# Stand_Sensor.net
KiCad netlist of a schematic drawn in EAGLE
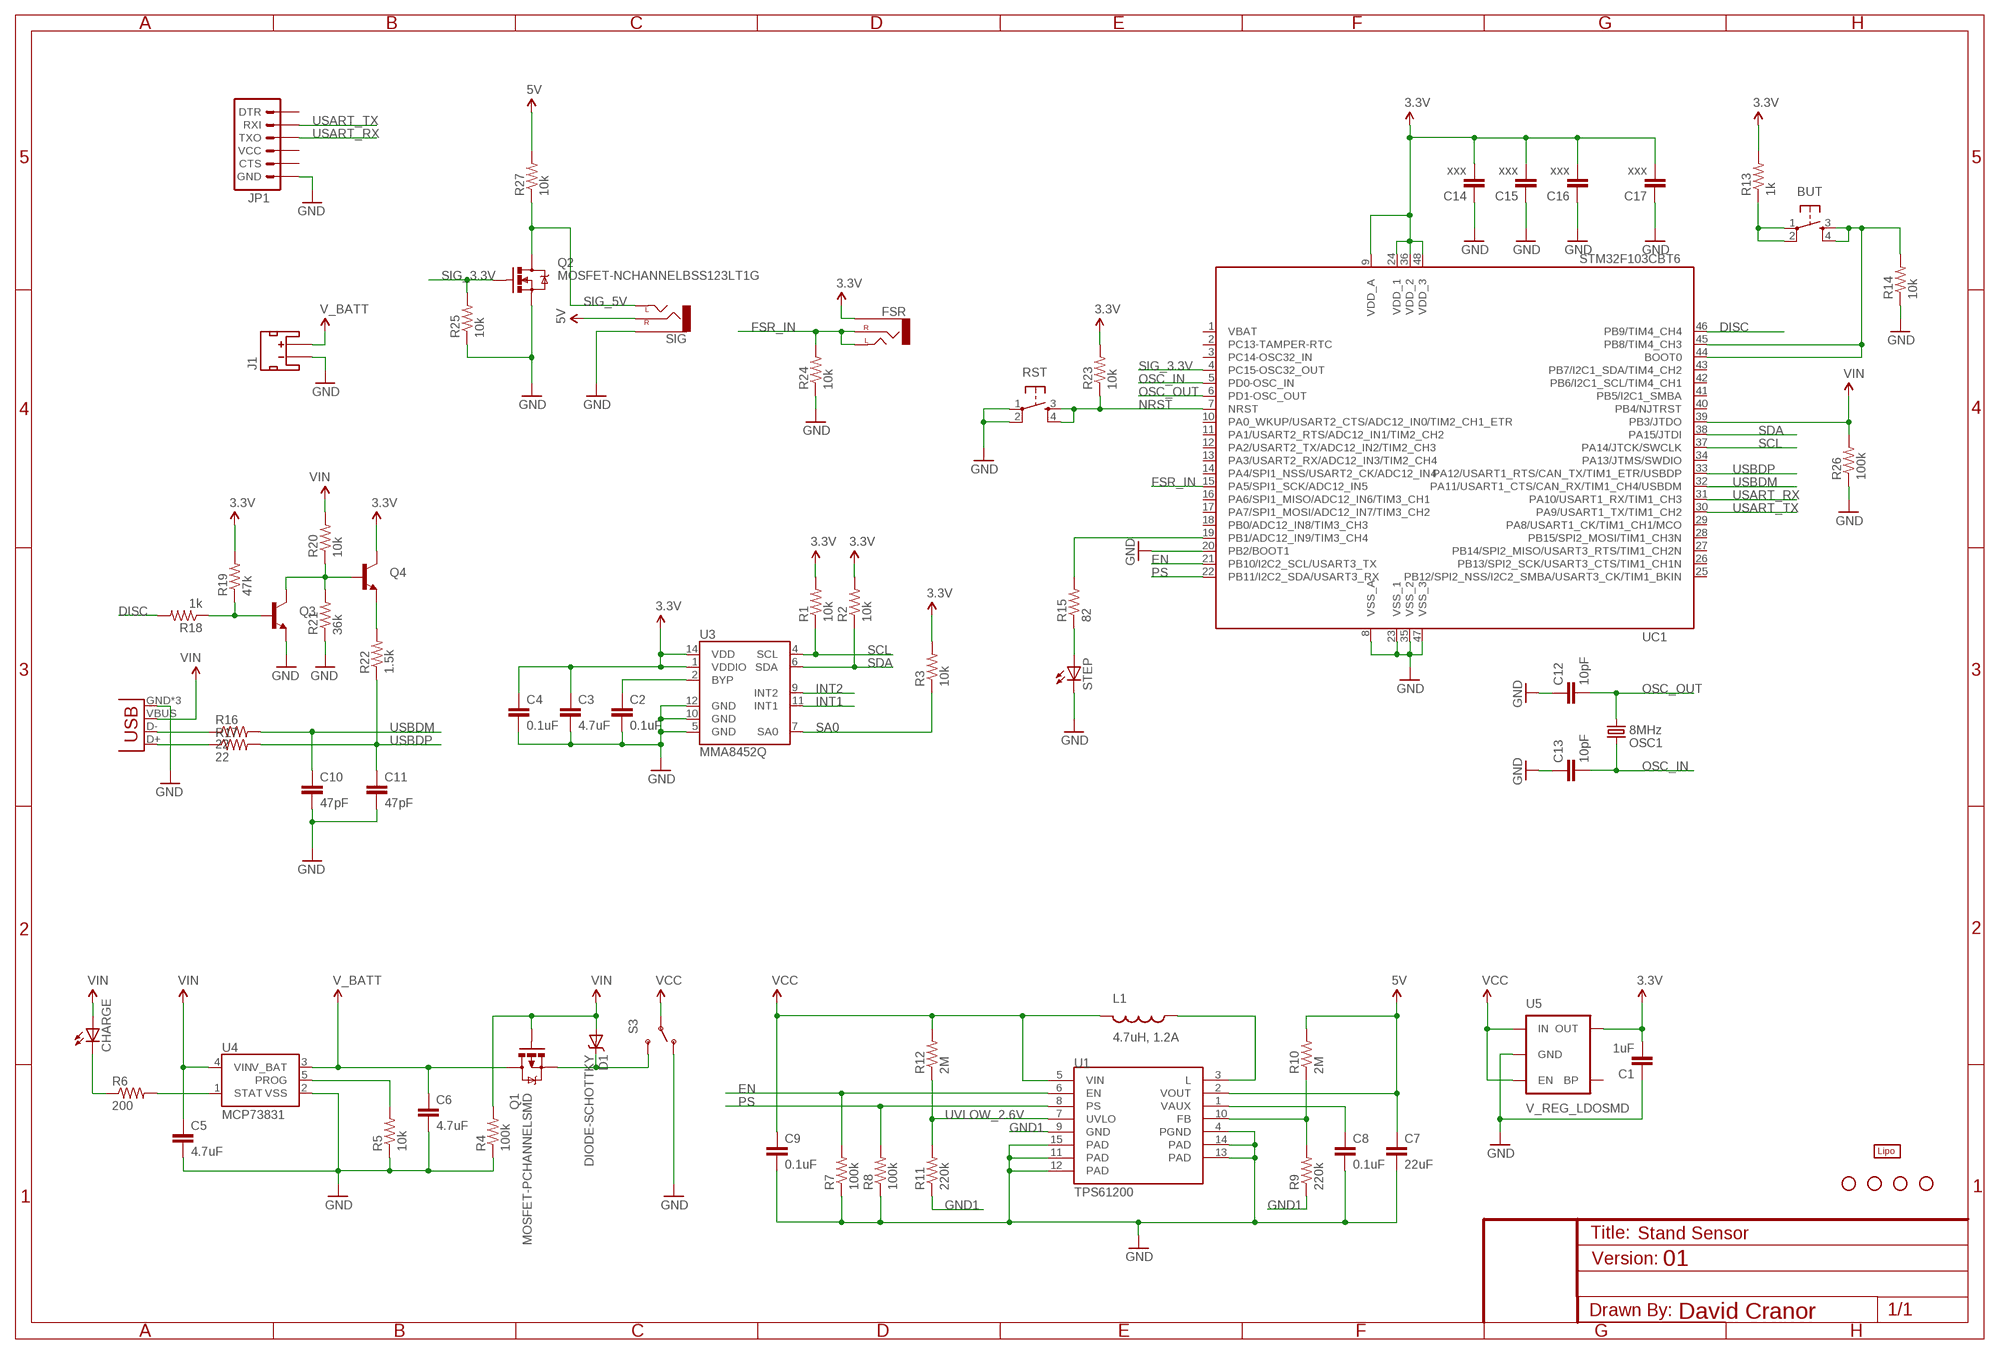
[diagram p0: schematic, sheet 1]

(export (version "E")
  (design (tool "Eeschema 10.0.6"))
  (components
    (comp (ref "BUT")
      (value "TAC_SWITCHSMD")
      (footprint "eagle-import:TACTILE_SWITCH_SMD")
      (libsource (lib "eagle-import") (part "TAC_SWITCHSMD"))
    )
    (comp (ref "C1")
      (value "1uF")
      (footprint "eagle-import:1206")
      (libsource (lib "eagle-import") (part "CAP1206"))
    )
    (comp (ref "C2")
      (value "0.1uF")
      (footprint "eagle-import:1206")
      (libsource (lib "eagle-import") (part "CAP1206"))
    )
    (comp (ref "C3")
      (value "4.7uF")
      (footprint "eagle-import:1206")
      (libsource (lib "eagle-import") (part "CAP1206"))
    )
    (comp (ref "C4")
      (value "0.1uF")
      (footprint "eagle-import:1206")
      (libsource (lib "eagle-import") (part "CAP1206"))
    )
    (comp (ref "C5")
      (value "4.7uF")
      (footprint "eagle-import:1206")
      (libsource (lib "eagle-import") (part "CAP1206"))
    )
    (comp (ref "C6")
      (value "4.7uF")
      (footprint "eagle-import:1206")
      (libsource (lib "eagle-import") (part "CAP1206"))
    )
    (comp (ref "C7")
      (value "22uF")
      (footprint "eagle-import:1206")
      (libsource (lib "eagle-import") (part "CAP1206"))
    )
    (comp (ref "C8")
      (value "0.1uF")
      (footprint "eagle-import:1206")
      (libsource (lib "eagle-import") (part "CAP1206"))
    )
    (comp (ref "C9")
      (value "0.1uF")
      (footprint "eagle-import:1206")
      (libsource (lib "eagle-import") (part "CAP1206"))
    )
    (comp (ref "C10")
      (value "47pF")
      (footprint "eagle-import:1206")
      (libsource (lib "eagle-import") (part "CAP1206"))
    )
    (comp (ref "C11")
      (value "47pF")
      (footprint "eagle-import:1206")
      (libsource (lib "eagle-import") (part "CAP1206"))
    )
    (comp (ref "C12")
      (value "10pF")
      (footprint "eagle-import:1206")
      (libsource (lib "eagle-import") (part "CAP1206"))
    )
    (comp (ref "C13")
      (value "10pF")
      (footprint "eagle-import:1206")
      (libsource (lib "eagle-import") (part "CAP1206"))
    )
    (comp (ref "C14")
      (value "xxx")
      (footprint "eagle-import:1206")
      (libsource (lib "eagle-import") (part "CAP1206"))
    )
    (comp (ref "C15")
      (value "xxx")
      (footprint "eagle-import:1206")
      (libsource (lib "eagle-import") (part "CAP1206"))
    )
    (comp (ref "C16")
      (value "xxx")
      (footprint "eagle-import:1206")
      (libsource (lib "eagle-import") (part "CAP1206"))
    )
    (comp (ref "C17")
      (value "xxx")
      (footprint "eagle-import:1206")
      (libsource (lib "eagle-import") (part "CAP1206"))
    )
    (comp (ref "CHARGE")
      (value "LED1206")
      (footprint "eagle-import:LED-1206")
      (libsource (lib "eagle-import") (part "LED1206"))
    )
    (comp (ref "D1")
      (value "DIODE-SCHOTTKY")
      (footprint "eagle-import:SOD-523")
      (libsource (lib "eagle-import") (part "DIODE-SCHOTTKY"))
    )
    (comp (ref "FSR")
      (value "AUDIO-JACKPTH")
      (footprint "eagle-import:AUDIO-JACK")
      (libsource (lib "eagle-import") (part "AUDIO-JACKPTH"))
    )
    (comp (ref "J1")
      (value "JST_2MM_MALE")
      (footprint "eagle-import:JST-2-SMD")
      (libsource (lib "eagle-import") (part "JST_2MM_MALE"))
    )
    (comp (ref "JP1")
      (value "ARDUINO_SERIAL_PROGRAMSMD")
      (footprint "eagle-import:1X06-SMD")
      (libsource (lib "eagle-import") (part "ARDUINO_SERIAL_PROGRAMSMD"))
    )
    (comp (ref "L1")
      (value "4.7uH, 1.2A")
      (footprint "eagle-import:CDRH2D09")
      (libsource (lib "eagle-import") (part "INDUCTOR."))
    )
    (comp (ref "OSC1")
      (value "8MHz")
      (footprint "eagle-import:CRYSTAL-SMD-5X3")
      (libsource (lib "eagle-import") (part "CRYSTAL5X3"))
    )
    (comp (ref "Q1")
      (value "MOSFET-PCHANNELSMD")
      (footprint "eagle-import:SOT23-3")
      (libsource (lib "eagle-import") (part "MOSFET-PCHANNELSMD"))
    )
    (comp (ref "Q2")
      (value "MOSFET-NCHANNELBSS123LT1G")
      (footprint "eagle-import:SOT23")
      (libsource (lib "eagle-import") (part "MOSFET-NCHANNELBSS123LT1G"))
    )
    (comp (ref "Q3")
      (value "TRANSISTOR_NPNSOT23")
      (footprint "eagle-import:SOT23")
      (libsource (lib "eagle-import") (part "TRANSISTOR_NPNSOT23"))
    )
    (comp (ref "Q4")
      (value "TRANSISTOR_NPNSOT23")
      (footprint "eagle-import:SOT23")
      (libsource (lib "eagle-import") (part "TRANSISTOR_NPNSOT23"))
    )
    (comp (ref "R1")
      (value "10k")
      (footprint "eagle-import:1206")
      (libsource (lib "eagle-import") (part "RESISTOR1206"))
    )
    (comp (ref "R2")
      (value "10k")
      (footprint "eagle-import:1206")
      (libsource (lib "eagle-import") (part "RESISTOR1206"))
    )
    (comp (ref "R3")
      (value "10k")
      (footprint "eagle-import:1206")
      (libsource (lib "eagle-import") (part "RESISTOR1206"))
    )
    (comp (ref "R4")
      (value "100k")
      (footprint "eagle-import:1206")
      (libsource (lib "eagle-import") (part "RESISTOR1206"))
    )
    (comp (ref "R5")
      (value "10k")
      (footprint "eagle-import:1206")
      (libsource (lib "eagle-import") (part "RESISTOR1206"))
    )
    (comp (ref "R6")
      (value "200")
      (footprint "eagle-import:1206")
      (libsource (lib "eagle-import") (part "RESISTOR1206"))
    )
    (comp (ref "R7")
      (value "100k")
      (footprint "eagle-import:1206")
      (libsource (lib "eagle-import") (part "RESISTOR1206"))
    )
    (comp (ref "R8")
      (value "100k")
      (footprint "eagle-import:1206")
      (libsource (lib "eagle-import") (part "RESISTOR1206"))
    )
    (comp (ref "R9")
      (value "220k")
      (footprint "eagle-import:1206")
      (libsource (lib "eagle-import") (part "RESISTOR1206"))
    )
    (comp (ref "R10")
      (value "2M")
      (footprint "eagle-import:1206")
      (libsource (lib "eagle-import") (part "RESISTOR1206"))
    )
    (comp (ref "R11")
      (value "220k")
      (footprint "eagle-import:1206")
      (libsource (lib "eagle-import") (part "RESISTOR1206"))
    )
    (comp (ref "R12")
      (value "2M")
      (footprint "eagle-import:1206")
      (libsource (lib "eagle-import") (part "RESISTOR1206"))
    )
    (comp (ref "R13")
      (value "1k")
      (footprint "eagle-import:1206")
      (libsource (lib "eagle-import") (part "RESISTOR1206"))
    )
    (comp (ref "R14")
      (value "10k")
      (footprint "eagle-import:1206")
      (libsource (lib "eagle-import") (part "RESISTOR1206"))
    )
    (comp (ref "R15")
      (value "82")
      (footprint "eagle-import:1206")
      (libsource (lib "eagle-import") (part "RESISTOR1206"))
    )
    (comp (ref "R16")
      (value "22")
      (footprint "eagle-import:1206")
      (libsource (lib "eagle-import") (part "RESISTOR1206"))
    )
    (comp (ref "R17")
      (value "22")
      (footprint "eagle-import:1206")
      (libsource (lib "eagle-import") (part "RESISTOR1206"))
    )
    (comp (ref "R18")
      (value "1k")
      (footprint "eagle-import:1206")
      (libsource (lib "eagle-import") (part "RESISTOR1206"))
    )
    (comp (ref "R19")
      (value "47k")
      (footprint "eagle-import:1206")
      (libsource (lib "eagle-import") (part "RESISTOR1206"))
    )
    (comp (ref "R20")
      (value "10k")
      (footprint "eagle-import:1206")
      (libsource (lib "eagle-import") (part "RESISTOR1206"))
    )
    (comp (ref "R21")
      (value "36k")
      (footprint "eagle-import:1206")
      (libsource (lib "eagle-import") (part "RESISTOR1206"))
    )
    (comp (ref "R22")
      (value "1.5k")
      (footprint "eagle-import:1206")
      (libsource (lib "eagle-import") (part "RESISTOR1206"))
    )
    (comp (ref "R23")
      (value "10k")
      (footprint "eagle-import:1206")
      (libsource (lib "eagle-import") (part "RESISTOR1206"))
    )
    (comp (ref "R24")
      (value "10k")
      (footprint "eagle-import:1206")
      (libsource (lib "eagle-import") (part "RESISTOR1206"))
    )
    (comp (ref "R25")
      (value "10k")
      (footprint "eagle-import:1206")
      (libsource (lib "eagle-import") (part "RESISTOR1206"))
    )
    (comp (ref "R26")
      (value "100k")
      (footprint "eagle-import:1206")
      (libsource (lib "eagle-import") (part "RESISTOR1206"))
    )
    (comp (ref "R27")
      (value "10k")
      (footprint "eagle-import:1206")
      (libsource (lib "eagle-import") (part "RESISTOR1206"))
    )
    (comp (ref "RST")
      (value "TAC_SWITCHSMD")
      (footprint "eagle-import:TACTILE_SWITCH_SMD")
      (libsource (lib "eagle-import") (part "TAC_SWITCHSMD"))
    )
    (comp (ref "S3")
      (value "SWITCH-SPDTSMD")
      (footprint "eagle-import:AYZ0202")
      (libsource (lib "eagle-import") (part "SWITCH-SPDTSMD"))
    )
    (comp (ref "SIG")
      (value "AUDIO-JACKPTH")
      (footprint "eagle-import:AUDIO-JACK")
      (libsource (lib "eagle-import") (part "AUDIO-JACKPTH"))
    )
    (comp (ref "STANDOFF1")
      (value "STAND-OFF")
      (footprint "eagle-import:STAND-OFF")
      (libsource (lib "eagle-import") (part "STAND-OFF"))
    )
    (comp (ref "STANDOFF2")
      (value "STAND-OFF")
      (footprint "eagle-import:STAND-OFF")
      (libsource (lib "eagle-import") (part "STAND-OFF"))
    )
    (comp (ref "STANDOFF3")
      (value "STAND-OFF")
      (footprint "eagle-import:STAND-OFF")
      (libsource (lib "eagle-import") (part "STAND-OFF"))
    )
    (comp (ref "STANDOFF4")
      (value "STAND-OFF")
      (footprint "eagle-import:STAND-OFF")
      (libsource (lib "eagle-import") (part "STAND-OFF"))
    )
    (comp (ref "STEP")
      (value "LED1206")
      (footprint "eagle-import:LED-1206")
      (libsource (lib "eagle-import") (part "LED1206"))
    )
    (comp (ref "U$1")
      (value "LIPO-OUTLINE2000")
      (footprint "eagle-import:LIPO-2000")
      (libsource (lib "eagle-import") (part "LIPO-OUTLINE2000"))
    )
    (comp (ref "U1")
      (value "TPS61200")
      (footprint "eagle-import:QFN-10_PAD")
      (libsource (lib "eagle-import") (part "TPS61200"))
    )
    (comp (ref "U3")
      (value "MMA8452Q")
      (footprint "eagle-import:QFN-16_0.5MM")
      (libsource (lib "eagle-import") (part "MMA8452Q"))
    )
    (comp (ref "U4")
      (value "MCP73831")
      (footprint "eagle-import:SOT23-5")
      (libsource (lib "eagle-import") (part "MCP73831"))
    )
    (comp (ref "U5")
      (value "V_REG_LDOSMD")
      (footprint "eagle-import:SOT23-5")
      (libsource (lib "eagle-import") (part "V_REG_LDOSMD"))
    )
    (comp (ref "UC1")
      (value "STM32F103CBT6")
      (footprint "eagle-import:LQFP48")
      (libsource (lib "eagle-import") (part "STM32F103CB"))
    )
    (comp (ref "USB")
      (value "USB-MICROB")
      (footprint "eagle-import:USB-MICROB")
      (libsource (lib "eagle-import") (part "USB-MICROB"))
    )
  )
  (nets
    (net (code "1") (name "/DISC") (class "Default")
      (node (ref "R18") (pin "2") (pinfunction "2_2") (pintype "passive"))
      (node (ref "UC1") (pin "46") (pinfunction "PB9/TIM4_CH4_46") (pintype "input"))
    )
    (net (code "2") (name "/EN") (class "Default")
      (node (ref "R7") (pin "2") (pinfunction "2_2") (pintype "passive"))
      (node (ref "U1") (pin "6") (pinfunction "EN_6") (pintype "input"))
      (node (ref "UC1") (pin "21") (pinfunction "PB10/I2C2_SCL/USART3_TX_21") (pintype "input"))
    )
    (net (code "3") (name "/FSR_IN") (class "Default")
      (node (ref "FSR") (pin "RING") (pinfunction "RIGHT_RING") (pintype "bidirectional"))
      (node (ref "FSR") (pin "TIP") (pinfunction "LEFT_TIP") (pintype "bidirectional"))
      (node (ref "R24") (pin "2") (pinfunction "2_2") (pintype "passive"))
      (node (ref "UC1") (pin "15") (pinfunction "PA5/SPI1_SCK/ADC12_IN5_15") (pintype "bidirectional"))
    )
    (net (code "4") (name "/GND1") (class "Default")
      (node (ref "R11") (pin "1") (pinfunction "1_1") (pintype "passive"))
      (node (ref "R9") (pin "1") (pinfunction "1_1") (pintype "passive"))
      (node (ref "U1") (pin "9") (pinfunction "GND_9") (pintype "power_in"))
    )
    (net (code "5") (name "/INT1") (class "Default")
      (node (ref "U3") (pin "11") (pinfunction "INT1_11") (pintype "bidirectional"))
    )
    (net (code "6") (name "/INT2") (class "Default")
      (node (ref "U3") (pin "9") (pinfunction "INT2_9") (pintype "bidirectional"))
    )
    (net (code "7") (name "/NRST") (class "Default")
      (node (ref "R23") (pin "1") (pinfunction "1_1") (pintype "passive"))
      (node (ref "RST") (pin "3") (pinfunction "3_3") (pintype "passive"))
      (node (ref "RST") (pin "4") (pinfunction "4_4") (pintype "passive"))
      (node (ref "UC1") (pin "7") (pinfunction "NRST_7") (pintype "input"))
    )
    (net (code "8") (name "/OSC_IN") (class "Default")
      (node (ref "C13") (pin "2") (pinfunction "2_2") (pintype "passive"))
      (node (ref "OSC1") (pin "3") (pinfunction "2_3") (pintype "passive"))
      (node (ref "UC1") (pin "5") (pinfunction "PD0-OSC_IN_5") (pintype "input"))
    )
    (net (code "9") (name "/OSC_OUT") (class "Default")
      (node (ref "C12") (pin "2") (pinfunction "2_2") (pintype "passive"))
      (node (ref "OSC1") (pin "1") (pinfunction "1_1") (pintype "passive"))
      (node (ref "UC1") (pin "6") (pinfunction "PD1-OSC_OUT_6") (pintype "input"))
    )
    (net (code "10") (name "/PS") (class "Default")
      (node (ref "R8") (pin "2") (pinfunction "2_2") (pintype "passive"))
      (node (ref "U1") (pin "8") (pinfunction "PS_8") (pintype "input"))
      (node (ref "UC1") (pin "22") (pinfunction "PB11/I2C2_SDA/USART3_RX_22") (pintype "input"))
    )
    (net (code "11") (name "/SA0") (class "Default")
      (node (ref "R3") (pin "1") (pinfunction "1_1") (pintype "passive"))
      (node (ref "U3") (pin "7") (pinfunction "SA0_7") (pintype "bidirectional"))
    )
    (net (code "12") (name "/SCL") (class "Default")
      (node (ref "R1") (pin "1") (pinfunction "1_1") (pintype "passive"))
      (node (ref "U3") (pin "4") (pinfunction "SCL_4") (pintype "bidirectional"))
      (node (ref "UC1") (pin "37") (pinfunction "PA14/JTCK/SWCLK_37") (pintype "bidirectional"))
    )
    (net (code "13") (name "/SDA") (class "Default")
      (node (ref "R2") (pin "1") (pinfunction "1_1") (pintype "passive"))
      (node (ref "U3") (pin "6") (pinfunction "SDA_6") (pintype "bidirectional"))
      (node (ref "UC1") (pin "38") (pinfunction "PA15/JTDI_38") (pintype "bidirectional"))
    )
    (net (code "14") (name "/SIG_3.3V") (class "Default")
      (node (ref "Q2") (pin "1") (pinfunction "G_1") (pintype "passive"))
      (node (ref "R25") (pin "2") (pinfunction "2_2") (pintype "passive"))
      (node (ref "UC1") (pin "4") (pinfunction "PC15-OSC32_OUT_4") (pintype "input"))
    )
    (net (code "15") (name "/SIG_5V") (class "Default")
      (node (ref "Q2") (pin "3") (pinfunction "D_3") (pintype "passive"))
      (node (ref "R27") (pin "1") (pinfunction "1_1") (pintype "passive"))
      (node (ref "SIG") (pin "TIP") (pinfunction "LEFT_TIP") (pintype "bidirectional"))
    )
    (net (code "16") (name "/USART_RX") (class "Default")
      (node (ref "JP1") (pin "3") (pinfunction "TXO_3") (pintype "passive"))
      (node (ref "UC1") (pin "31") (pinfunction "PA10/USART1_RX/TIM1_CH3_31") (pintype "bidirectional"))
    )
    (net (code "17") (name "/USART_TX") (class "Default")
      (node (ref "JP1") (pin "2") (pinfunction "RXI_2") (pintype "passive"))
      (node (ref "UC1") (pin "30") (pinfunction "PA9/USART1_TX/TIM1_CH2_30") (pintype "input"))
    )
    (net (code "18") (name "/USBDM") (class "Default")
      (node (ref "C10") (pin "1") (pinfunction "1_1") (pintype "passive"))
      (node (ref "R16") (pin "2") (pinfunction "2_2") (pintype "passive"))
      (node (ref "UC1") (pin "32") (pinfunction "PA11/USART1_CTS/CAN_RX/TIM1_CH4/USBDM_32") (pintype "bidirectional"))
    )
    (net (code "19") (name "/USBDP") (class "Default")
      (node (ref "C11") (pin "1") (pinfunction "1_1") (pintype "passive"))
      (node (ref "R17") (pin "2") (pinfunction "2_2") (pintype "passive"))
      (node (ref "R22") (pin "1") (pinfunction "1_1") (pintype "passive"))
      (node (ref "UC1") (pin "33") (pinfunction "PA12/USART1_RTS/CAN_TX/TIM1_ETR/USBDP_33") (pintype "bidirectional"))
    )
    (net (code "20") (name "/UVLOW_2.6V") (class "Default")
      (node (ref "R11") (pin "2") (pinfunction "2_2") (pintype "passive"))
      (node (ref "R12") (pin "1") (pinfunction "1_1") (pintype "passive"))
      (node (ref "U1") (pin "7") (pinfunction "UVLO_7") (pintype "passive"))
    )
    (net (code "21") (name "/VBAT") (class "Default")
      (node (ref "UC1") (pin "1") (pinfunction "VBAT_1") (pintype "power_in"))
    )
    (net (code "22") (name "3.3V") (class "Default")
      (node (ref "C1") (pin "2") (pinfunction "2_2") (pintype "passive"))
      (node (ref "C14") (pin "2") (pinfunction "2_2") (pintype "passive"))
      (node (ref "C15") (pin "2") (pinfunction "2_2") (pintype "passive"))
      (node (ref "C16") (pin "2") (pinfunction "2_2") (pintype "passive"))
      (node (ref "C17") (pin "2") (pinfunction "2_2") (pintype "passive"))
      (node (ref "C3") (pin "1") (pinfunction "1_1") (pintype "passive"))
      (node (ref "C4") (pin "1") (pinfunction "1_1") (pintype "passive"))
      (node (ref "FSR") (pin "SLEEVE") (pinfunction "SLEEVE_SLEEVE") (pintype "bidirectional"))
      (node (ref "Q4") (pin "3") (pinfunction "C_3") (pintype "passive"))
      (node (ref "R1") (pin "2") (pinfunction "2_2") (pintype "passive"))
      (node (ref "R13") (pin "2") (pinfunction "2_2") (pintype "passive"))
      (node (ref "R19") (pin "2") (pinfunction "2_2") (pintype "passive"))
      (node (ref "R2") (pin "2") (pinfunction "2_2") (pintype "passive"))
      (node (ref "R23") (pin "2") (pinfunction "2_2") (pintype "passive"))
      (node (ref "R3") (pin "2") (pinfunction "2_2") (pintype "passive"))
      (node (ref "U3") (pin "1") (pinfunction "VDDIO_1") (pintype "bidirectional"))
      (node (ref "U3") (pin "14") (pinfunction "VDD_14") (pintype "bidirectional"))
      (node (ref "U5") (pin "5") (pinfunction "OUT_5") (pintype "passive"))
      (node (ref "UC1") (pin "24") (pinfunction "VDD_1_24") (pintype "power_in"))
      (node (ref "UC1") (pin "36") (pinfunction "VDD_2_36") (pintype "power_in"))
      (node (ref "UC1") (pin "48") (pinfunction "VDD_3_48") (pintype "power_in"))
      (node (ref "UC1") (pin "9") (pinfunction "VDD_A_9") (pintype "power_in"))
    )
    (net (code "23") (name "5V") (class "Default")
      (node (ref "C7") (pin "1") (pinfunction "1_1") (pintype "passive"))
      (node (ref "R10") (pin "2") (pinfunction "2_2") (pintype "passive"))
      (node (ref "R27") (pin "2") (pinfunction "2_2") (pintype "passive"))
      (node (ref "SIG") (pin "RING") (pinfunction "RIGHT_RING") (pintype "bidirectional"))
      (node (ref "U1") (pin "2") (pinfunction "VOUT_2") (pintype "passive"))
    )
    (net (code "24") (name "GND") (class "Default")
      (node (ref "C1") (pin "1") (pinfunction "1_1") (pintype "passive"))
      (node (ref "C10") (pin "2") (pinfunction "2_2") (pintype "passive"))
      (node (ref "C11") (pin "2") (pinfunction "2_2") (pintype "passive"))
      (node (ref "C12") (pin "1") (pinfunction "1_1") (pintype "passive"))
      (node (ref "C13") (pin "1") (pinfunction "1_1") (pintype "passive"))
      (node (ref "C14") (pin "1") (pinfunction "1_1") (pintype "passive"))
      (node (ref "C15") (pin "1") (pinfunction "1_1") (pintype "passive"))
      (node (ref "C16") (pin "1") (pinfunction "1_1") (pintype "passive"))
      (node (ref "C17") (pin "1") (pinfunction "1_1") (pintype "passive"))
      (node (ref "C2") (pin "2") (pinfunction "2_2") (pintype "passive"))
      (node (ref "C3") (pin "2") (pinfunction "2_2") (pintype "passive"))
      (node (ref "C4") (pin "2") (pinfunction "2_2") (pintype "passive"))
      (node (ref "C5") (pin "2") (pinfunction "2_2") (pintype "passive"))
      (node (ref "C6") (pin "2") (pinfunction "2_2") (pintype "passive"))
      (node (ref "C7") (pin "2") (pinfunction "2_2") (pintype "passive"))
      (node (ref "C8") (pin "2") (pinfunction "2_2") (pintype "passive"))
      (node (ref "C9") (pin "2") (pinfunction "2_2") (pintype "passive"))
      (node (ref "J1") (pin "1") (pinfunction "-_1") (pintype "bidirectional"))
      (node (ref "JP1") (pin "6") (pinfunction "GND_6") (pintype "passive"))
      (node (ref "Q2") (pin "2") (pinfunction "S_2") (pintype "passive"))
      (node (ref "Q3") (pin "2") (pinfunction "E_2") (pintype "passive"))
      (node (ref "R14") (pin "1") (pinfunction "1_1") (pintype "passive"))
      (node (ref "R21") (pin "1") (pinfunction "1_1") (pintype "passive"))
      (node (ref "R24") (pin "1") (pinfunction "1_1") (pintype "passive"))
      (node (ref "R25") (pin "1") (pinfunction "1_1") (pintype "passive"))
      (node (ref "R26") (pin "1") (pinfunction "1_1") (pintype "passive"))
      (node (ref "R4") (pin "1") (pinfunction "1_1") (pintype "passive"))
      (node (ref "R5") (pin "1") (pinfunction "1_1") (pintype "passive"))
      (node (ref "R7") (pin "1") (pinfunction "1_1") (pintype "passive"))
      (node (ref "R8") (pin "1") (pinfunction "1_1") (pintype "passive"))
      (node (ref "RST") (pin "1") (pinfunction "1_1") (pintype "passive"))
      (node (ref "RST") (pin "2") (pinfunction "2_2") (pintype "passive"))
      (node (ref "S3") (pin "1") (pinfunction "O_1") (pintype "passive"))
      (node (ref "SIG") (pin "SLEEVE") (pinfunction "SLEEVE_SLEEVE") (pintype "bidirectional"))
      (node (ref "STEP") (pin "C") (pinfunction "C_C") (pintype "passive"))
      (node (ref "U1") (pin "11") (pinfunction "PAD_11") (pintype "power_in"))
      (node (ref "U1") (pin "12") (pinfunction "PAD_12") (pintype "power_in"))
      (node (ref "U1") (pin "13") (pinfunction "PAD_13") (pintype "power_in"))
      (node (ref "U1") (pin "14") (pinfunction "PAD_14") (pintype "power_in"))
      (node (ref "U1") (pin "15") (pinfunction "PAD_15") (pintype "power_in"))
      (node (ref "U1") (pin "4") (pinfunction "PGND_4") (pintype "power_in"))
      (node (ref "U3") (pin "10") (pinfunction "GND_10") (pintype "bidirectional"))
      (node (ref "U3") (pin "12") (pinfunction "GND_12") (pintype "bidirectional"))
      (node (ref "U3") (pin "5") (pinfunction "GND_5") (pintype "bidirectional"))
      (node (ref "U4") (pin "2") (pinfunction "VSS_2") (pintype "power_in"))
      (node (ref "U5") (pin "2") (pinfunction "GND_2") (pintype "input"))
      (node (ref "UC1") (pin "20") (pinfunction "PB2/BOOT1_20") (pintype "bidirectional"))
      (node (ref "UC1") (pin "23") (pinfunction "VSS_1_23") (pintype "power_in"))
      (node (ref "UC1") (pin "35") (pinfunction "VSS_2_35") (pintype "power_in"))
      (node (ref "UC1") (pin "47") (pinfunction "VSS_3_47") (pintype "power_in"))
      (node (ref "UC1") (pin "8") (pinfunction "VSS_A_8") (pintype "power_in"))
      (node (ref "USB") (pin "GND") (pinfunction "GND_GND") (pintype "bidirectional"))
      (node (ref "USB") (pin "MT1") (pinfunction "GND_MT1") (pintype "bidirectional"))
      (node (ref "USB") (pin "MT2") (pinfunction "GND_MT2") (pintype "bidirectional"))
    )
    (net (code "25") (name "Net-(BUT-Pad1)") (class "Default")
      (node (ref "BUT") (pin "1") (pinfunction "1_1") (pintype "passive"))
      (node (ref "BUT") (pin "2") (pinfunction "2_2") (pintype "passive"))
      (node (ref "R13") (pin "1") (pinfunction "1_1") (pintype "passive"))
    )
    (net (code "26") (name "Net-(CHARGE-PadC)") (class "Default")
      (node (ref "CHARGE") (pin "C") (pinfunction "C_C") (pintype "passive"))
      (node (ref "R6") (pin "1") (pinfunction "1_1") (pintype "passive"))
    )
    (net (code "27") (name "Net-(L1-1)") (class "Default")
      (node (ref "L1") (pin "P$1") (pinfunction "1_P$1") (pintype "passive"))
      (node (ref "U1") (pin "3") (pinfunction "L_3") (pintype "passive"))
    )
    (net (code "28") (name "Net-(Q1-S)") (class "Default")
      (node (ref "D1") (pin "C") (pinfunction "C_C") (pintype "passive"))
      (node (ref "Q1") (pin "2") (pinfunction "S_2") (pintype "passive"))
      (node (ref "S3") (pin "3") (pinfunction "S_3") (pintype "passive"))
    )
    (net (code "29") (name "Net-(Q3-B)") (class "Default")
      (node (ref "Q3") (pin "1") (pinfunction "B_1") (pintype "passive"))
      (node (ref "R18") (pin "1") (pinfunction "1_1") (pintype "passive"))
      (node (ref "R19") (pin "1") (pinfunction "1_1") (pintype "passive"))
    )
    (net (code "30") (name "Net-(Q3-C)") (class "Default")
      (node (ref "Q3") (pin "3") (pinfunction "C_3") (pintype "passive"))
      (node (ref "Q4") (pin "1") (pinfunction "B_1") (pintype "passive"))
      (node (ref "R20") (pin "1") (pinfunction "1_1") (pintype "passive"))
      (node (ref "R21") (pin "2") (pinfunction "2_2") (pintype "passive"))
    )
    (net (code "31") (name "Net-(Q4-E)") (class "Default")
      (node (ref "Q4") (pin "2") (pinfunction "E_2") (pintype "passive"))
      (node (ref "R22") (pin "2") (pinfunction "2_2") (pintype "passive"))
    )
    (net (code "32") (name "Net-(R15-Pad1)") (class "Default")
      (node (ref "R15") (pin "1") (pinfunction "1_1") (pintype "passive"))
      (node (ref "STEP") (pin "A") (pinfunction "A_A") (pintype "passive"))
    )
    (net (code "33") (name "Net-(R16-Pad1)") (class "Default")
      (node (ref "R16") (pin "1") (pinfunction "1_1") (pintype "passive"))
      (node (ref "USB") (pin "D-") (pinfunction "D-_D-") (pintype "bidirectional"))
    )
    (net (code "34") (name "Net-(R17-Pad1)") (class "Default")
      (node (ref "R17") (pin "1") (pinfunction "1_1") (pintype "passive"))
      (node (ref "USB") (pin "D+") (pinfunction "D+_D+") (pintype "bidirectional"))
    )
    (net (code "35") (name "Net-(U1-FB)") (class "Default")
      (node (ref "R10") (pin "1") (pinfunction "1_1") (pintype "passive"))
      (node (ref "R9") (pin "2") (pinfunction "2_2") (pintype "passive"))
      (node (ref "U1") (pin "10") (pinfunction "FB_10") (pintype "passive"))
    )
    (net (code "36") (name "Net-(U1-VAUX)") (class "Default")
      (node (ref "C8") (pin "1") (pinfunction "1_1") (pintype "passive"))
      (node (ref "U1") (pin "1") (pinfunction "VAUX_1") (pintype "passive"))
    )
    (net (code "37") (name "Net-(U3-BYP)") (class "Default")
      (node (ref "C2") (pin "1") (pinfunction "1_1") (pintype "passive"))
      (node (ref "U3") (pin "2") (pinfunction "BYP_2") (pintype "bidirectional"))
    )
    (net (code "38") (name "Net-(U4-PROG)") (class "Default")
      (node (ref "R5") (pin "2") (pinfunction "2_2") (pintype "passive"))
      (node (ref "U4") (pin "5") (pinfunction "PROG_5") (pintype "input"))
    )
    (net (code "39") (name "Net-(U4-STAT)") (class "Default")
      (node (ref "R6") (pin "2") (pinfunction "2_2") (pintype "passive"))
      (node (ref "U4") (pin "1") (pinfunction "STAT_1") (pintype "output"))
    )
    (net (code "40") (name "Net-(UC1-BOOT0)") (class "Default")
      (node (ref "BUT") (pin "3") (pinfunction "3_3") (pintype "passive"))
      (node (ref "BUT") (pin "4") (pinfunction "4_4") (pintype "passive"))
      (node (ref "R14") (pin "2") (pinfunction "2_2") (pintype "passive"))
      (node (ref "UC1") (pin "44") (pinfunction "BOOT0_44") (pintype "input"))
      (node (ref "UC1") (pin "45") (pinfunction "PB8/TIM4_CH3_45") (pintype "bidirectional"))
    )
    (net (code "41") (name "Net-(UC1-PB1{slash}ADC12_IN9{slash}TIM3_CH4)") (class "Default")
      (node (ref "R15") (pin "2") (pinfunction "2_2") (pintype "passive"))
      (node (ref "UC1") (pin "19") (pinfunction "PB1/ADC12_IN9/TIM3_CH4_19") (pintype "bidirectional"))
    )
    (net (code "42") (name "VCC") (class "Default")
      (node (ref "C9") (pin "1") (pinfunction "1_1") (pintype "passive"))
      (node (ref "L1") (pin "P$2") (pinfunction "2_P$2") (pintype "passive"))
      (node (ref "R12") (pin "2") (pinfunction "2_2") (pintype "passive"))
      (node (ref "S3") (pin "2") (pinfunction "P_2") (pintype "passive"))
      (node (ref "U1") (pin "5") (pinfunction "VIN_5") (pintype "power_in"))
      (node (ref "U5") (pin "1") (pinfunction "IN_1") (pintype "input"))
      (node (ref "U5") (pin "3") (pinfunction "EN_3") (pintype "input"))
    )
    (net (code "43") (name "VIN") (class "Default")
      (node (ref "C5") (pin "1") (pinfunction "1_1") (pintype "passive"))
      (node (ref "CHARGE") (pin "A") (pinfunction "A_A") (pintype "passive"))
      (node (ref "D1") (pin "A") (pinfunction "A_A") (pintype "passive"))
      (node (ref "Q1") (pin "1") (pinfunction "G_1") (pintype "passive"))
      (node (ref "R20") (pin "2") (pinfunction "2_2") (pintype "passive"))
      (node (ref "R26") (pin "2") (pinfunction "2_2") (pintype "passive"))
      (node (ref "R4") (pin "2") (pinfunction "2_2") (pintype "passive"))
      (node (ref "U4") (pin "4") (pinfunction "VIN_4") (pintype "power_in"))
      (node (ref "UC1") (pin "39") (pinfunction "PB3/JTDO_39") (pintype "bidirectional"))
      (node (ref "USB") (pin "VBUS") (pinfunction "VBUS_VBUS") (pintype "bidirectional"))
    )
    (net (code "44") (name "V_BATT") (class "Default")
      (node (ref "C6") (pin "1") (pinfunction "1_1") (pintype "passive"))
      (node (ref "J1") (pin "2") (pinfunction "+_2") (pintype "bidirectional"))
      (node (ref "Q1") (pin "3") (pinfunction "D_3") (pintype "passive"))
      (node (ref "U4") (pin "3") (pinfunction "V_BAT_3") (pintype "power_in"))
    )
    (net (code "45") (name "unconnected-(J1-PAD1-PadNC1)") (class "Default")
      (node (ref "J1") (pin "NC1") (pinfunction "PAD1_NC1") (pintype "bidirectional"))
    )
    (net (code "46") (name "unconnected-(J1-PAD2-PadNC2)") (class "Default")
      (node (ref "J1") (pin "NC2") (pinfunction "PAD2_NC2") (pintype "bidirectional"))
    )
    (net (code "47") (name "unconnected-(JP1-CTS-Pad5)") (class "Default")
      (node (ref "JP1") (pin "5") (pinfunction "CTS_5") (pintype "passive"))
    )
    (net (code "48") (name "unconnected-(JP1-DTR-Pad1)") (class "Default")
      (node (ref "JP1") (pin "1") (pinfunction "DTR_1") (pintype "passive"))
    )
    (net (code "49") (name "unconnected-(JP1-VCC-Pad4)") (class "Default")
      (node (ref "JP1") (pin "4") (pinfunction "VCC_4") (pintype "passive"))
    )
    (net (code "50") (name "unconnected-(U5-BP-Pad4)") (class "Default")
      (node (ref "U5") (pin "4") (pinfunction "BP_4") (pintype "input"))
    )
    (net (code "51") (name "unconnected-(UC1-PA0_WKUP{slash}USART2_CTS{slash}ADC12_IN0{slash}TIM2_CH1_ETR-Pad10)") (class "Default")
      (node (ref "UC1") (pin "10") (pinfunction "PA0_WKUP/USART2_CTS/ADC12_IN0/TIM2_CH1_ETR_10") (pintype "bidirectional"))
    )
    (net (code "52") (name "unconnected-(UC1-PA1{slash}USART2_RTS{slash}ADC12_IN1{slash}TIM2_CH2-Pad11)") (class "Default")
      (node (ref "UC1") (pin "11") (pinfunction "PA1/USART2_RTS/ADC12_IN1/TIM2_CH2_11") (pintype "bidirectional"))
    )
    (net (code "53") (name "unconnected-(UC1-PA2{slash}USART2_TX{slash}ADC12_IN2{slash}TIM2_CH3-Pad12)") (class "Default")
      (node (ref "UC1") (pin "12") (pinfunction "PA2/USART2_TX/ADC12_IN2/TIM2_CH3_12") (pintype "bidirectional"))
    )
    (net (code "54") (name "unconnected-(UC1-PA3{slash}USART2_RX{slash}ADC12_IN3{slash}TIM2_CH4-Pad13)") (class "Default")
      (node (ref "UC1") (pin "13") (pinfunction "PA3/USART2_RX/ADC12_IN3/TIM2_CH4_13") (pintype "bidirectional"))
    )
    (net (code "55") (name "unconnected-(UC1-PA4{slash}SPI1_NSS{slash}USART2_CK{slash}ADC12_IN4-Pad14)") (class "Default")
      (node (ref "UC1") (pin "14") (pinfunction "PA4/SPI1_NSS/USART2_CK/ADC12_IN4_14") (pintype "bidirectional"))
    )
    (net (code "56") (name "unconnected-(UC1-PA6{slash}SPI1_MISO{slash}ADC12_IN6{slash}TIM3_CH1-Pad16)") (class "Default")
      (node (ref "UC1") (pin "16") (pinfunction "PA6/SPI1_MISO/ADC12_IN6/TIM3_CH1_16") (pintype "bidirectional"))
    )
    (net (code "57") (name "unconnected-(UC1-PA7{slash}SPI1_MOSI{slash}ADC12_IN7{slash}TIM3_CH2-Pad17)") (class "Default")
      (node (ref "UC1") (pin "17") (pinfunction "PA7/SPI1_MOSI/ADC12_IN7/TIM3_CH2_17") (pintype "bidirectional"))
    )
    (net (code "58") (name "unconnected-(UC1-PA8{slash}USART1_CK{slash}TIM1_CH1{slash}MCO-Pad29)") (class "Default")
      (node (ref "UC1") (pin "29") (pinfunction "PA8/USART1_CK/TIM1_CH1/MCO_29") (pintype "bidirectional"))
    )
    (net (code "59") (name "unconnected-(UC1-PA13{slash}JTMS{slash}SWDIO-Pad34)") (class "Default")
      (node (ref "UC1") (pin "34") (pinfunction "PA13/JTMS/SWDIO_34") (pintype "bidirectional"))
    )
    (net (code "60") (name "unconnected-(UC1-PB0{slash}ADC12_IN8{slash}TIM3_CH3-Pad18)") (class "Default")
      (node (ref "UC1") (pin "18") (pinfunction "PB0/ADC12_IN8/TIM3_CH3_18") (pintype "bidirectional"))
    )
    (net (code "61") (name "unconnected-(UC1-PB4{slash}NJTRST-Pad40)") (class "Default")
      (node (ref "UC1") (pin "40") (pinfunction "PB4/NJTRST_40") (pintype "bidirectional"))
    )
    (net (code "62") (name "unconnected-(UC1-PB5{slash}I2C1_SMBA-Pad41)") (class "Default")
      (node (ref "UC1") (pin "41") (pinfunction "PB5/I2C1_SMBA_41") (pintype "input"))
    )
    (net (code "63") (name "unconnected-(UC1-PB6{slash}I2C1_SCL{slash}TIM4_CH1-Pad42)") (class "Default")
      (node (ref "UC1") (pin "42") (pinfunction "PB6/I2C1_SCL/TIM4_CH1_42") (pintype "input"))
    )
    (net (code "64") (name "unconnected-(UC1-PB7{slash}I2C1_SDA{slash}TIM4_CH2-Pad43)") (class "Default")
      (node (ref "UC1") (pin "43") (pinfunction "PB7/I2C1_SDA/TIM4_CH2_43") (pintype "bidirectional"))
    )
    (net (code "65") (name "unconnected-(UC1-PB12{slash}SPI2_NSS{slash}I2C2_SMBA{slash}USART3_CK{slash}TIM1_BKIN-Pad25)") (class "Default")
      (node (ref "UC1") (pin "25") (pinfunction "PB12/SPI2_NSS/I2C2_SMBA/USART3_CK/TIM1_BKIN_25") (pintype "input"))
    )
    (net (code "66") (name "unconnected-(UC1-PB13{slash}SPI2_SCK{slash}USART3_CTS{slash}TIM1_CH1N-Pad26)") (class "Default")
      (node (ref "UC1") (pin "26") (pinfunction "PB13/SPI2_SCK/USART3_CTS/TIM1_CH1N_26") (pintype "input"))
    )
    (net (code "67") (name "unconnected-(UC1-PB14{slash}SPI2_MISO{slash}USART3_RTS{slash}TIM1_CH2N-Pad27)") (class "Default")
      (node (ref "UC1") (pin "27") (pinfunction "PB14/SPI2_MISO/USART3_RTS/TIM1_CH2N_27") (pintype "input"))
    )
    (net (code "68") (name "unconnected-(UC1-PB15{slash}SPI2_MOSI{slash}TIM1_CH3N-Pad28)") (class "Default")
      (node (ref "UC1") (pin "28") (pinfunction "PB15/SPI2_MOSI/TIM1_CH3N_28") (pintype "input"))
    )
    (net (code "69") (name "unconnected-(UC1-PC13-TAMPER-RTC-Pad2)") (class "Default")
      (node (ref "UC1") (pin "2") (pinfunction "PC13-TAMPER-RTC_2") (pintype "input"))
    )
    (net (code "70") (name "unconnected-(UC1-PC14-OSC32_IN-Pad3)") (class "Default")
      (node (ref "UC1") (pin "3") (pinfunction "PC14-OSC32_IN_3") (pintype "input"))
    )
  )
)
